# PROC099A_QSPI_Flash_Reference.net
KiCad netlist of a schematic drawn in Altium Designer
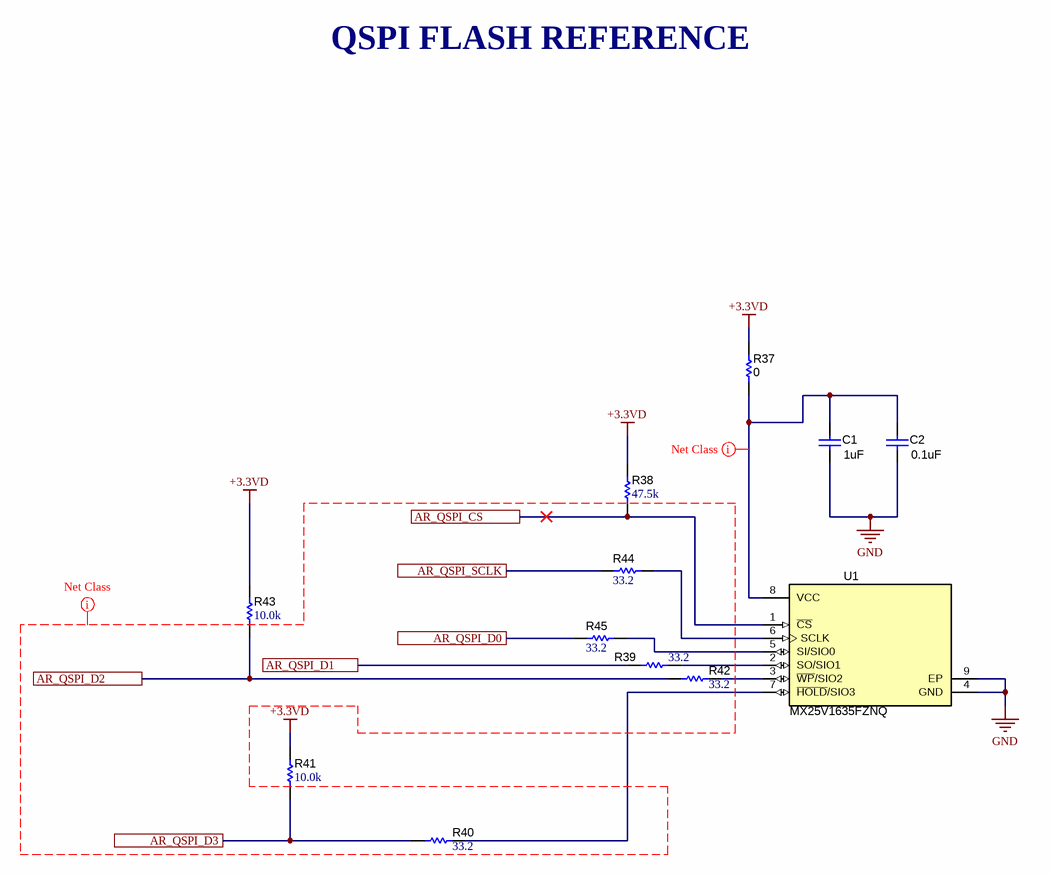
[diagram p0: PROC099A_QSPI_Flash_Reference.SchDoc]

(export (version "E")
  (design (tool "Eeschema 10.0.6"))
  (components
    (comp (ref "C1")
      (value "GCM188R71C105KA64D")
      (footprint "0603")
      (description "CAP, CERM, 1 uF, 16 V, +/- 10%, X7R, AEC-Q200 Grade 1, 0603")
      (fields
        (field (name "MANUFACTURER") "MuRata")
        (field (name "VALUEDISPLAYED") "1uF")
        (field (name "PUBLISHER") "Texas Instruments")
      )
      (libsource (lib "Altium Vault - TI") (part "Capacitor"))
    )
    (comp (ref "C2")
      (value "CGA2B3X7R1H104K050BB")
      (footprint "0402L")
      (description "CAP, CERM, 0.1 uF, 50 V, +/- 10%, X7R, AEC-Q200 Grade 1, 0402")
      (fields
        (field (name "MANUFACTURER") "TDK")
        (field (name "VALUEDISPLAYED") "0.1uF")
        (field (name "PUBLISHER") "Texas Instruments")
      )
      (libsource (lib "Altium Vault - TI") (part "Capacitor"))
    )
    (comp (ref "R37")
      (value "ERJ-2GE0R00X")
      (footprint "0402L")
      (description "RES, 0, 5%, 0.063 W, 0402")
      (fields
        (field (name "MANUFACTURER") "Panasonic")
        (field (name "VALUEDISPLAYED") "0")
        (field (name "PUBLISHER") "Texas Instruments")
      )
      (libsource (lib "Altium Vault - TI") (part "Resistor"))
    )
    (comp (ref "R38")
      (value "CRCW040247K5FKED")
      (footprint "0402L")
      (description "RES, 47.5 k, 1%, 0.063 W, AEC-Q200 Grade 0, 0402")
      (fields (field (name "MANUFACTURER") "Vishay-Dale") (field (name "VALUEDISPLAYED") "47.5k"))
      (libsource (lib "Altium Vault - TI") (part "Resistor"))
    )
    (comp (ref "R39")
      (value "CRCW020133R2FNED")
      (footprint "0201_Silk")
      (description "RES, 33.2, 1%, 0.05 W, 0201")
      (fields (field (name "MANUFACTURER") "Vishay-Dale") (field (name "VALUEDISPLAYED") "33.2"))
      (libsource (lib "Altium Vault - TI") (part "Resistor"))
    )
    (comp (ref "R40")
      (value "CRCW020133R2FNED")
      (footprint "0201_Silk")
      (description "RES, 33.2, 1%, 0.05 W, 0201")
      (fields (field (name "MANUFACTURER") "Vishay-Dale") (field (name "VALUEDISPLAYED") "33.2"))
      (libsource (lib "Altium Vault - TI") (part "Resistor"))
    )
    (comp (ref "R41")
      (value "CRCW040210K0FKED")
      (footprint "0402L")
      (description "RES, 10.0 k, 1%, 0.063 W, AEC-Q200 Grade 0, 0402")
      (fields (field (name "MANUFACTURER") "Vishay-Dale") (field (name "VALUEDISPLAYED") "10.0k"))
      (libsource (lib "Altium Vault - TI") (part "Resistor"))
    )
    (comp (ref "R42")
      (value "CRCW020133R2FNED")
      (footprint "0201_Silk")
      (description "RES, 33.2, 1%, 0.05 W, 0201")
      (fields (field (name "MANUFACTURER") "Vishay-Dale") (field (name "VALUEDISPLAYED") "33.2"))
      (libsource (lib "Altium Vault - TI") (part "Resistor"))
    )
    (comp (ref "R43")
      (value "CRCW040210K0FKED")
      (footprint "0402L")
      (description "RES, 10.0 k, 1%, 0.063 W, AEC-Q200 Grade 0, 0402")
      (fields (field (name "MANUFACTURER") "Vishay-Dale") (field (name "VALUEDISPLAYED") "10.0k"))
      (libsource (lib "Altium Vault - TI") (part "Resistor"))
    )
    (comp (ref "R44")
      (value "CRCW020133R2FNED")
      (footprint "0201_Silk")
      (description "RES, 33.2, 1%, 0.05 W, 0201")
      (fields (field (name "MANUFACTURER") "Vishay-Dale") (field (name "VALUEDISPLAYED") "33.2"))
      (libsource (lib "Altium Vault - TI") (part "Resistor"))
    )
    (comp (ref "R45")
      (value "CRCW020133R2FNED")
      (footprint "0201_Silk")
      (description "RES, 33.2, 1%, 0.05 W, 0201")
      (fields (field (name "MANUFACTURER") "Vishay-Dale") (field (name "VALUEDISPLAYED") "33.2"))
      (libsource (lib "Altium Vault - TI") (part "Resistor"))
    )
    (comp (ref "U1")
      (value "MX25V1635FZNQ")
      (footprint "WSON-8L_6x5MM_EP")
      (description "2.3V-3.6V, 16M-BIT [x 1/x 2/x 4] CMOS FLASH Memory, WSON-8")
      (fields (field (name "MANUFACTURER") "Macronix International Co., LTD"))
      (libsource (lib "Altium Vault - TI") (part "MX25V1635FZ"))
    )
  )
  (nets
    (net (code "1") (name "+3.3VD") (class "Default")
      (node (ref "R37") (pin "1") (pinfunction "1_1") (pintype "passive"))
      (node (ref "R38") (pin "2") (pinfunction "2_2") (pintype "passive"))
      (node (ref "R41") (pin "2") (pinfunction "2_2") (pintype "passive"))
      (node (ref "R43") (pin "2") (pinfunction "2_2") (pintype "passive"))
    )
    (net (code "2") (name "/AR_QSPI_CS") (class "Default")
      (node (ref "R38") (pin "1") (pinfunction "1_1") (pintype "passive"))
      (node (ref "U1") (pin "1") (pinfunction "CS_1") (pintype "input"))
    )
    (net (code "3") (name "/AR_QSPI_D0") (class "Default")
      (node (ref "R45") (pin "2") (pinfunction "2_2") (pintype "passive"))
    )
    (net (code "4") (name "/AR_QSPI_D1") (class "Default")
      (node (ref "R39") (pin "1") (pinfunction "1_1") (pintype "passive"))
    )
    (net (code "5") (name "/AR_QSPI_D2") (class "Default")
      (node (ref "R42") (pin "1") (pinfunction "1_1") (pintype "passive"))
      (node (ref "R43") (pin "1") (pinfunction "1_1") (pintype "passive"))
    )
    (net (code "6") (name "/AR_QSPI_D3") (class "Default")
      (node (ref "R40") (pin "2") (pinfunction "2_2") (pintype "passive"))
      (node (ref "R41") (pin "1") (pinfunction "1_1") (pintype "passive"))
    )
    (net (code "7") (name "/AR_QSPI_SCLK") (class "Default")
      (node (ref "R44") (pin "2") (pinfunction "2_2") (pintype "passive"))
    )
    (net (code "8") (name "GND") (class "Default")
      (node (ref "C1") (pin "1") (pinfunction "1_1") (pintype "passive"))
      (node (ref "C2") (pin "1") (pinfunction "1_1") (pintype "passive"))
      (node (ref "U1") (pin "4") (pinfunction "GND_4") (pintype "power_in"))
      (node (ref "U1") (pin "9") (pinfunction "EP_9") (pintype "passive"))
    )
    (net (code "9") (name "Net-(U1-SCLK)") (class "Default")
      (node (ref "R44") (pin "1") (pinfunction "1_1") (pintype "passive"))
      (node (ref "U1") (pin "6") (pinfunction "SCLK_6") (pintype "input"))
    )
    (net (code "10") (name "Net-(U1-SI{slash}SIO0)") (class "Default")
      (node (ref "R45") (pin "1") (pinfunction "1_1") (pintype "passive"))
      (node (ref "U1") (pin "5") (pinfunction "SI/SIO0_5") (pintype "bidirectional"))
    )
    (net (code "11") (name "Net-(U1-SO{slash}SIO1)") (class "Default")
      (node (ref "R39") (pin "2") (pinfunction "2_2") (pintype "passive"))
      (node (ref "U1") (pin "2") (pinfunction "SO/SIO1_2") (pintype "bidirectional"))
    )
    (net (code "12") (name "Net-(U1-VCC)") (class "Default")
      (node (ref "C1") (pin "2") (pinfunction "2_2") (pintype "passive"))
      (node (ref "C2") (pin "2") (pinfunction "2_2") (pintype "passive"))
      (node (ref "R37") (pin "2") (pinfunction "2_2") (pintype "passive"))
      (node (ref "U1") (pin "8") (pinfunction "VCC_8") (pintype "power_in"))
    )
    (net (code "13") (name "Net-(U1-~{HOLD}{slash}SIO3)") (class "Default")
      (node (ref "R40") (pin "1") (pinfunction "1_1") (pintype "passive"))
      (node (ref "U1") (pin "7") (pinfunction "~{HOLD}/SIO3_7") (pintype "bidirectional"))
    )
    (net (code "14") (name "Net-(U1-~{WP}{slash}SIO2)") (class "Default")
      (node (ref "R42") (pin "2") (pinfunction "2_2") (pintype "passive"))
      (node (ref "U1") (pin "3") (pinfunction "~{WP}/SIO2_3") (pintype "bidirectional"))
    )
  )
)
